# Heaters.net
KiCad netlist of a schematic drawn in Altium Designer
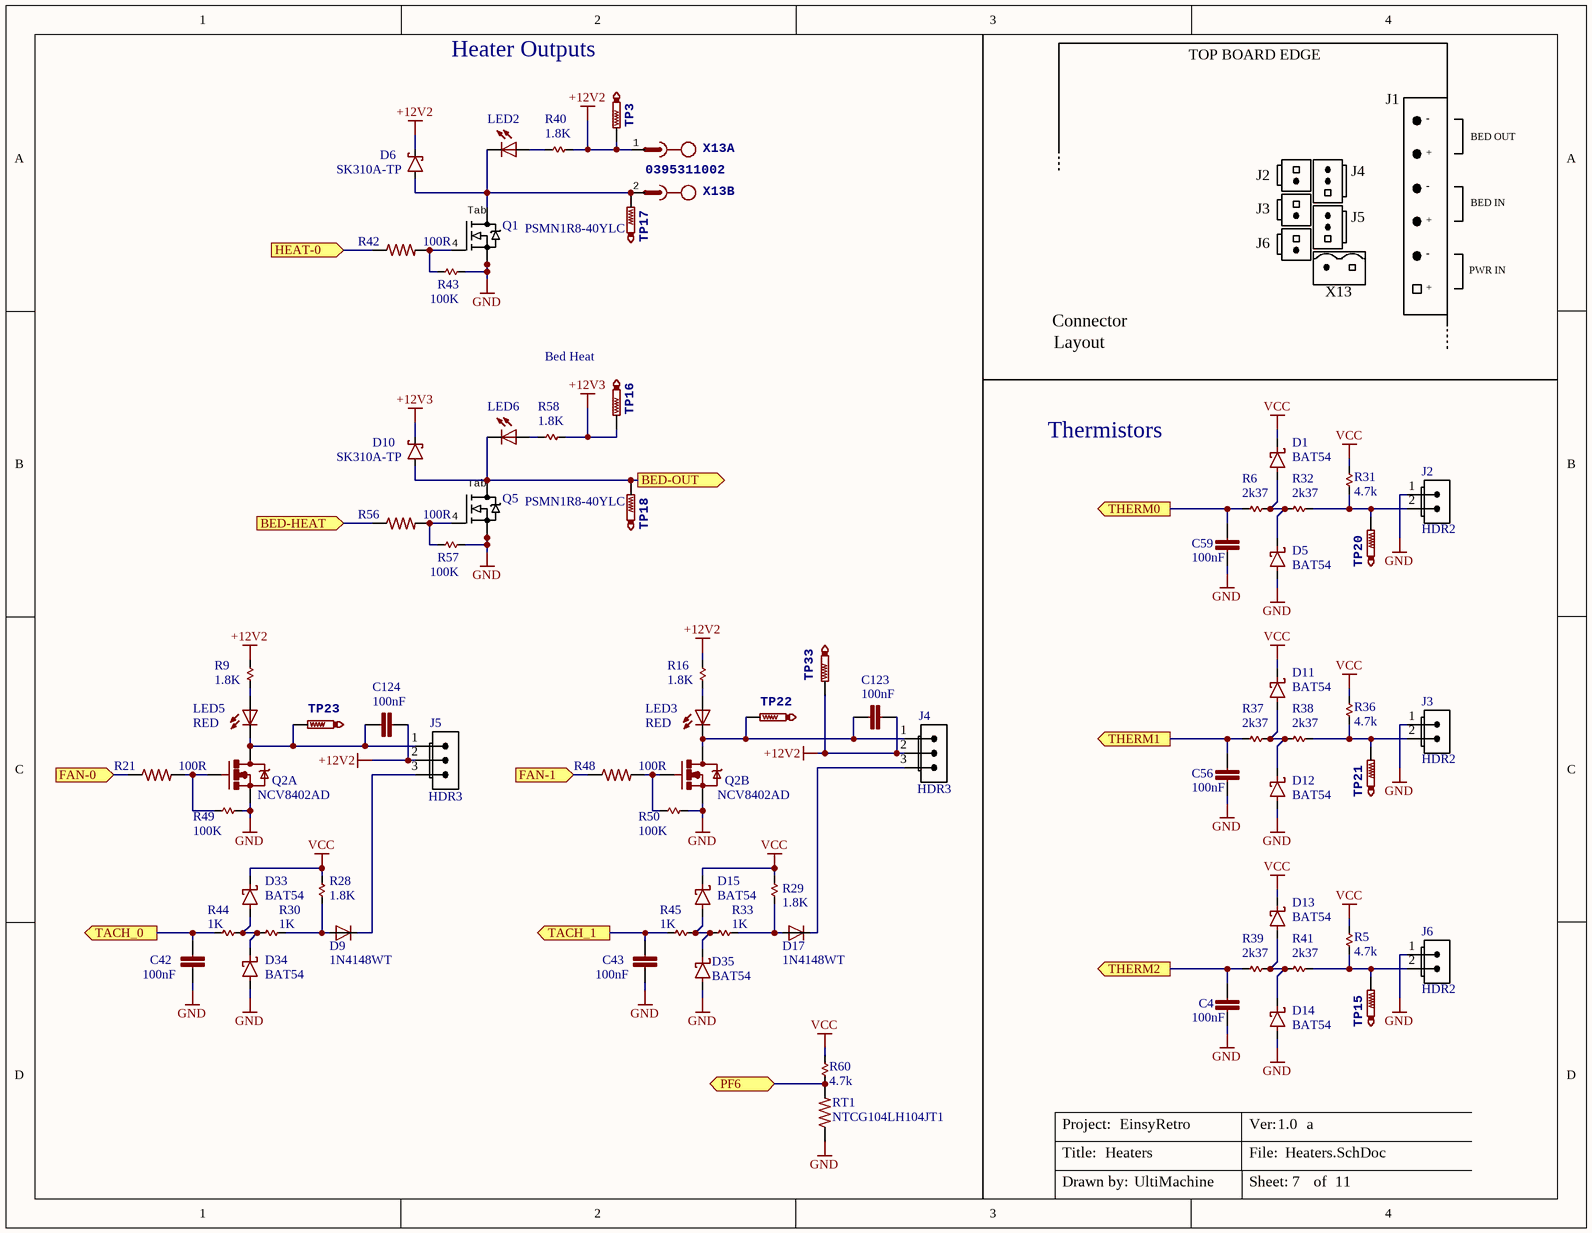
[diagram p0: Heaters.SchDoc]

(export (version "E")
  (design (tool "Eeschema 10.0.6"))
  (components
    (comp (ref "C4")
      (value "100nF")
      (footprint "C0402")
      (description "CAP CER 0402 100nF 16V 10% X7R")
      (fields (field (name "MANUFACTURER") "Murata") (field (name "TOLERANCE") "+/- 10%"))
      (libsource (lib "") (part "GRM155R71C104KA88D_1"))
    )
    (comp (ref "C42")
      (value "100nF")
      (footprint "C0402")
      (description "CAP CER 0402 100nF 16V 10% X7R")
      (fields (field (name "MANUFACTURER") "Murata") (field (name "TOLERANCE") "+/- 10%"))
      (libsource (lib "") (part "GRM155R71C104KA88D_1"))
    )
    (comp (ref "C43")
      (value "100nF")
      (footprint "C0402")
      (description "CAP CER 0402 100nF 16V 10% X7R")
      (fields (field (name "MANUFACTURER") "Murata") (field (name "TOLERANCE") "+/- 10%"))
      (libsource (lib "") (part "GRM155R71C104KA88D_1"))
    )
    (comp (ref "C56")
      (value "100nF")
      (footprint "C0402")
      (description "CAP CER 0402 100nF 16V 10% X7R")
      (fields (field (name "MANUFACTURER") "Murata") (field (name "TOLERANCE") "+/- 10%"))
      (libsource (lib "") (part "GRM155R71C104KA88D_1"))
    )
    (comp (ref "C59")
      (value "100nF")
      (footprint "C0402")
      (description "CAP CER 0402 100nF 16V 10% X7R")
      (fields (field (name "MANUFACTURER") "Murata") (field (name "TOLERANCE") "+/- 10%"))
      (libsource (lib "") (part "GRM155R71C104KA88D_1"))
    )
    (comp (ref "C123")
      (value "100nF")
      (footprint "C0402")
      (description "CAP CER 0402 100nF 16V 10% X7R")
      (fields (field (name "MANUFACTURER") "Murata") (field (name "TOLERANCE") "+/- 10%"))
      (libsource (lib "3Delight") (part "GRM155R71C104KA88D"))
    )
    (comp (ref "C124")
      (value "100nF")
      (footprint "C0402")
      (description "CAP CER 0402 100nF 16V 10% X7R")
      (fields (field (name "MANUFACTURER") "Murata") (field (name "TOLERANCE") "+/- 10%"))
      (libsource (lib "3Delight") (part "GRM155R71C104KA88D"))
    )
    (comp (ref "D1")
      (value "BAT54")
      (footprint "SOD523_IPC")
      (description "Diode Schottky 30V 100mA Surface Mount SOD-523")
      (fields (field (name "MANUFACTURER") "Diodes Incorporated") (field (name "TOLERANCE") "NA"))
      (libsource (lib "3Delight") (part "BAT54WT-7"))
    )
    (comp (ref "D5")
      (value "BAT54")
      (footprint "SOD523_IPC")
      (description "Diode Schottky 30V 100mA Surface Mount SOD-523")
      (fields (field (name "MANUFACTURER") "Diodes Incorporated") (field (name "TOLERANCE") "NA"))
      (libsource (lib "3Delight") (part "BAT54WT-7"))
    )
    (comp (ref "D6")
      (value "SK310A-TP")
      (footprint "SMA-SM")
      (description "DIODE Schottky 3A SMA")
      (fields (field (name "MANUFACTURER") "MCC") (field (name "PART") "Schottky Diode 100V 3A"))
      (libsource (lib "Diodes") (part "SK310A"))
    )
    (comp (ref "D9")
      (value "1N4148WT")
      (footprint "SOD523")
      (description "DIODE SOD523")
      (fields (field (name "MANUFACTURER") "Fairchild") (field (name "TOLERANCE") "NA"))
      (libsource (lib "3Delight") (part "1N4148WT"))
    )
    (comp (ref "D10")
      (value "SK310A-TP")
      (footprint "SMA-SM")
      (description "DIODE Schottky 3A SMA")
      (fields (field (name "MANUFACTURER") "MCC") (field (name "PART") "Schottky Diode 100V 3A"))
      (libsource (lib "Diodes") (part "SK310A"))
    )
    (comp (ref "D11")
      (value "BAT54")
      (footprint "SOD523_IPC")
      (description "Diode Schottky 30V 100mA Surface Mount SOD-523")
      (fields (field (name "MANUFACTURER") "Diodes Incorporated") (field (name "TOLERANCE") "NA"))
      (libsource (lib "3Delight") (part "BAT54WT-7"))
    )
    (comp (ref "D12")
      (value "BAT54")
      (footprint "SOD523_IPC")
      (description "Diode Schottky 30V 100mA Surface Mount SOD-523")
      (fields (field (name "MANUFACTURER") "Diodes Incorporated") (field (name "TOLERANCE") "NA"))
      (libsource (lib "3Delight") (part "BAT54WT-7"))
    )
    (comp (ref "D13")
      (value "BAT54")
      (footprint "SOD523_IPC")
      (description "Diode Schottky 30V 100mA Surface Mount SOD-523")
      (fields (field (name "MANUFACTURER") "Diodes Incorporated") (field (name "TOLERANCE") "NA"))
      (libsource (lib "3Delight") (part "BAT54WT-7"))
    )
    (comp (ref "D14")
      (value "BAT54")
      (footprint "SOD523_IPC")
      (description "Diode Schottky 30V 100mA Surface Mount SOD-523")
      (fields (field (name "MANUFACTURER") "Diodes Incorporated") (field (name "TOLERANCE") "NA"))
      (libsource (lib "3Delight") (part "BAT54WT-7"))
    )
    (comp (ref "D15")
      (value "BAT54")
      (footprint "SOD523_IPC")
      (description "Diode Schottky 30V 100mA Surface Mount SOD-523")
      (fields (field (name "MANUFACTURER") "Diodes Incorporated") (field (name "TOLERANCE") "NA"))
      (libsource (lib "3Delight") (part "BAT54WT-7"))
    )
    (comp (ref "D17")
      (value "1N4148WT")
      (footprint "SOD523")
      (description "DIODE SOD523")
      (fields (field (name "MANUFACTURER") "Fairchild") (field (name "TOLERANCE") "NA"))
      (libsource (lib "3Delight") (part "1N4148WT"))
    )
    (comp (ref "D33")
      (value "BAT54")
      (footprint "SOD523_IPC")
      (description "Diode Schottky 30V 100mA Surface Mount SOD-523")
      (fields (field (name "MANUFACTURER") "Diodes Incorporated") (field (name "TOLERANCE") "NA"))
      (libsource (lib "3Delight") (part "BAT54WT-7"))
    )
    (comp (ref "D34")
      (value "BAT54")
      (footprint "SOD523_IPC")
      (description "Diode Schottky 30V 100mA Surface Mount SOD-523")
      (fields (field (name "MANUFACTURER") "Diodes Incorporated") (field (name "TOLERANCE") "NA"))
      (libsource (lib "3Delight") (part "BAT54WT-7"))
    )
    (comp (ref "D35")
      (value "BAT54")
      (footprint "SOD523_IPC")
      (description "Diode Schottky 30V 100mA Surface Mount SOD-523")
      (fields (field (name "MANUFACTURER") "Diodes Incorporated") (field (name "TOLERANCE") "NA"))
      (libsource (lib "3Delight") (part "BAT54WT-7"))
    )
    (comp (ref "J2")
      (value "HDR2")
      (footprint "70543-02")
      (description "Connector 2pos")
      (fields (field (name "MANUFACTURER") "Molex") (field (name "PART") "10 Pin Conn"))
      (libsource (lib "Archim_0.4") (part "CONN 2PIN VERT 0.1{dblquote} SHRD LOCKING"))
    )
    (comp (ref "J3")
      (value "HDR2")
      (footprint "70543-02")
      (description "Connector 2pos")
      (fields (field (name "MANUFACTURER") "Molex") (field (name "PART") "10 Pin Conn"))
      (libsource (lib "Archim_0.4") (part "CONN 2PIN VERT 0.1{dblquote} SHRD LOCKING"))
    )
    (comp (ref "J4")
      (value "HDR3")
      (footprint "70543-03")
      (description "3 Positions Header, Shrouded Connector 0.100\" (2.54mm) Through Hole Gold")
      (fields (field (name "MANUFACTURER") "Molex") (field (name "PART") "3 Pin Conn VERT"))
      (libsource (lib "Archim_0.4") (part "CONN 3POS VERT 0.1{dblquote} SHRD LOCKING"))
    )
    (comp (ref "J5")
      (value "HDR3")
      (footprint "70543-03")
      (description "3 Positions Header, Shrouded Connector 0.100\" (2.54mm) Through Hole Gold")
      (fields (field (name "MANUFACTURER") "Molex") (field (name "PART") "3 Pin Conn VERT"))
      (libsource (lib "Archim_0.4") (part "CONN 3POS VERT 0.1{dblquote} SHRD LOCKING"))
    )
    (comp (ref "J6")
      (value "HDR2")
      (footprint "70543-02")
      (description "Connector 2pos")
      (fields (field (name "MANUFACTURER") "Molex") (field (name "PART") "10 Pin Conn"))
      (libsource (lib "Archim_0.4") (part "CONN 2PIN VERT 0.1{dblquote} SHRD LOCKING"))
    )
    (comp (ref "LED2")
      (value "RED")
      (footprint "LED2012120")
      (description "LED 0805 Red")
      (fields (field (name "MANUFACTURER") "Dialight") (field (name "TOLERANCE") "NA"))
      (libsource (lib "3Delight") (part "5988110107F"))
    )
    (comp (ref "LED3")
      (value "RED")
      (footprint "LED2012120")
      (description "LED 0805 Red")
      (fields
        (field (name "MANUFACTURER") "Dialight")
        (field (name "PART") "RED")
        (field (name "TOLERANCE") "NA")
      )
      (libsource (lib "3Delight") (part "5988110107F"))
    )
    (comp (ref "LED5")
      (value "RED")
      (footprint "LED2012120")
      (description "LED 0805 Red")
      (fields
        (field (name "MANUFACTURER") "Dialight")
        (field (name "PART") "RED")
        (field (name "TOLERANCE") "NA")
      )
      (libsource (lib "3Delight") (part "5988110107F"))
    )
    (comp (ref "LED6")
      (value "RED")
      (footprint "LED2012120")
      (description "LED 0805 Red")
      (fields (field (name "MANUFACTURER") "Dialight") (field (name "TOLERANCE") "NA"))
      (libsource (lib "3Delight") (part "5988110107F"))
    )
    (comp (ref "Q1")
      (value "PSMN1R8-40YLC")
      (footprint "SOT669")
      (description "MOSFET N-CH 40V 100A LFPAK")
      (fields (field (name "MANUFACTURER") "Nexperia") (field (name "TOLERANCE") "-NA-"))
      (libsource (lib "Transistors") (part "PSMN1R8-40YLC"))
    )
    (comp (ref "Q2")
      (value "NCV8402AD")
      (footprint "NCV8402AD-SOIC8")
      (description "IC DVR LOW SIDE 8-SOIC")
      (fields (field (name "MANUFACTURER") "On Semi") (field (name "PART") "NCV8402"))
      (libsource (lib "3Delight") (part "NCV8402AD"))
    )
    (comp (ref "Q5")
      (value "PSMN1R8-40YLC")
      (footprint "SOT669")
      (description "MOSFET N-CH 40V 100A LFPAK")
      (fields (field (name "MANUFACTURER") "Nexperia") (field (name "TOLERANCE") "-NA-"))
      (libsource (lib "Transistors") (part "PSMN1R8-40YLC"))
    )
    (comp (ref "R5")
      (value "4.7k")
      (footprint "R0402")
      (description "RES SMD 4.7K OHM 1% 1/16W 0402")
      (fields (field (name "MANUFACTURER") "Yageo") (field (name "TOLERANCE") "+/- 1%"))
      (libsource (lib "3Delight") (part "RC0402FR-074K7L"))
    )
    (comp (ref "R6")
      (value "2k37")
      (footprint "R0402")
      (description "RES SMD 2.37K OHM 1% 1/16W 0402")
      (fields (field (name "MANUFACTURER") "Yageo") (field (name "PART") "2.37k"))
      (libsource (lib "3Delight") (part "RC0402FR-072K37L"))
    )
    (comp (ref "R9")
      (value "1.8K")
      (footprint "R0402")
      (description "RES SMD 1.8K OHM 1% 1/16W 0402")
      (fields (field (name "MANUFACTURER") "Yageo") (field (name "PART") "1.8k"))
      (libsource (lib "3Delight") (part "RC0402FR-071K8L"))
    )
    (comp (ref "R16")
      (value "1.8K")
      (footprint "R0402")
      (description "RES SMD 1.8K OHM 1% 1/16W 0402")
      (fields (field (name "MANUFACTURER") "Yageo") (field (name "PART") "1.8k"))
      (libsource (lib "3Delight") (part "RC0402FR-071K8L"))
    )
    (comp (ref "R21")
      (value "100R")
      (footprint "R0402")
      (description "RES SMD 100 OHM 1% 1/16W 0402")
      (fields (field (name "MANUFACTURER") "Yageo") (field (name "PART") "100R 1% 0402"))
      (libsource (lib "Archim") (part "RES 100R 0402 1%"))
    )
    (comp (ref "R28")
      (value "1.8K")
      (footprint "R0402")
      (description "RES SMD 1.8K OHM 1% 1/16W 0402")
      (fields (field (name "MANUFACTURER") "Yageo") (field (name "PART") "1.8k"))
      (libsource (lib "3Delight") (part "RC0402FR-071K8L"))
    )
    (comp (ref "R29")
      (value "1.8K")
      (footprint "R0402")
      (description "RES SMD 1.8K OHM 1% 1/16W 0402")
      (fields (field (name "MANUFACTURER") "Yageo") (field (name "PART") "1.8k"))
      (libsource (lib "3Delight") (part "RC0402FR-071K8L"))
    )
    (comp (ref "R30")
      (value "1K")
      (footprint "R0402")
      (description "RES SMD 1K OHM 1% 1/16W 0402")
      (fields (field (name "MANUFACTURER") "Yageo") (field (name "PART") "1k"))
      (libsource (lib "3Delight") (part "RC0402FR-071KL"))
    )
    (comp (ref "R31")
      (value "4.7k")
      (footprint "R0402")
      (description "RES SMD 4.7K OHM 1% 1/16W 0402")
      (fields (field (name "MANUFACTURER") "Yageo") (field (name "TOLERANCE") "+/- 1%"))
      (libsource (lib "3Delight") (part "RC0402FR-074K7L"))
    )
    (comp (ref "R32")
      (value "2k37")
      (footprint "R0402")
      (description "RES SMD 2.37K OHM 1% 1/16W 0402")
      (fields (field (name "MANUFACTURER") "Yageo") (field (name "PART") "2.37k"))
      (libsource (lib "3Delight") (part "RC0402FR-072K37L"))
    )
    (comp (ref "R33")
      (value "1K")
      (footprint "R0402")
      (description "RES SMD 1K OHM 1% 1/16W 0402")
      (fields (field (name "MANUFACTURER") "Yageo") (field (name "PART") "1k"))
      (libsource (lib "3Delight") (part "RC0402FR-071KL"))
    )
    (comp (ref "R36")
      (value "4.7k")
      (footprint "R0402")
      (description "RES SMD 4.7K OHM 1% 1/16W 0402")
      (fields (field (name "MANUFACTURER") "Yageo") (field (name "TOLERANCE") "+/- 1%"))
      (libsource (lib "3Delight") (part "RC0402FR-074K7L"))
    )
    (comp (ref "R37")
      (value "2k37")
      (footprint "R0402")
      (description "RES SMD 2.37K OHM 1% 1/16W 0402")
      (fields (field (name "MANUFACTURER") "Yageo") (field (name "PART") "2.37k"))
      (libsource (lib "3Delight") (part "RC0402FR-072K37L"))
    )
    (comp (ref "R38")
      (value "2k37")
      (footprint "R0402")
      (description "RES SMD 2.37K OHM 1% 1/16W 0402")
      (fields (field (name "MANUFACTURER") "Yageo") (field (name "PART") "2.37k"))
      (libsource (lib "3Delight") (part "RC0402FR-072K37L"))
    )
    (comp (ref "R39")
      (value "2k37")
      (footprint "R0402")
      (description "RES SMD 2.37K OHM 1% 1/16W 0402")
      (fields (field (name "MANUFACTURER") "Yageo") (field (name "PART") "2.37k"))
      (libsource (lib "3Delight") (part "RC0402FR-072K37L"))
    )
    (comp (ref "R40")
      (value "1.8K")
      (footprint "R0402")
      (description "RES SMD 1.8K OHM 1% 1/16W 0402")
      (fields (field (name "MANUFACTURER") "Yageo") (field (name "PART") "1.8k"))
      (libsource (lib "3Delight") (part "RC0402FR-071K8L"))
    )
    (comp (ref "R41")
      (value "2k37")
      (footprint "R0402")
      (description "RES SMD 2.37K OHM 1% 1/16W 0402")
      (fields (field (name "MANUFACTURER") "Yageo") (field (name "PART") "2.37k"))
      (libsource (lib "3Delight") (part "RC0402FR-072K37L"))
    )
    (comp (ref "R42")
      (value "100R")
      (footprint "R0402")
      (description "RES SMD 100 OHM 1% 1/16W 0402")
      (fields (field (name "MANUFACTURER") "Yageo") (field (name "PART") "100R 1% 0402"))
      (libsource (lib "Archim") (part "RES 100R 0402 1%"))
    )
    (comp (ref "R43")
      (value "100K")
      (footprint "R0402")
      (description "RES 100K OHM 1% 1/16W 0402")
      (fields (field (name "MANUFACTURER") "Yageo") (field (name "TOLERANCE") "+/- 1%"))
      (libsource (lib "3Delight") (part "RC0402FR-07100KL"))
    )
    (comp (ref "R44")
      (value "1K")
      (footprint "R0402")
      (description "RES SMD 1K OHM 1% 1/16W 0402")
      (fields (field (name "MANUFACTURER") "Yageo") (field (name "PART") "1k"))
      (libsource (lib "3Delight") (part "RC0402FR-071KL"))
    )
    (comp (ref "R45")
      (value "1K")
      (footprint "R0402")
      (description "RES SMD 1K OHM 1% 1/16W 0402")
      (fields (field (name "MANUFACTURER") "Yageo") (field (name "PART") "1k"))
      (libsource (lib "3Delight") (part "RC0402FR-071KL"))
    )
    (comp (ref "R48")
      (value "100R")
      (footprint "R0402")
      (description "RES SMD 100 OHM 1% 1/16W 0402")
      (fields (field (name "MANUFACTURER") "Yageo") (field (name "PART") "100R 1% 0402"))
      (libsource (lib "Archim") (part "RES 100R 0402 1%"))
    )
    (comp (ref "R49")
      (value "100K")
      (footprint "R0402")
      (description "RES 100K OHM 1% 1/16W 0402")
      (fields (field (name "MANUFACTURER") "Yageo") (field (name "TOLERANCE") "+/- 1%"))
      (libsource (lib "3Delight") (part "RC0402FR-07100KL"))
    )
    (comp (ref "R50")
      (value "100K")
      (footprint "R0402")
      (description "RES 100K OHM 1% 1/16W 0402")
      (fields (field (name "MANUFACTURER") "Yageo") (field (name "TOLERANCE") "+/- 1%"))
      (libsource (lib "3Delight") (part "RC0402FR-07100KL"))
    )
    (comp (ref "R56")
      (value "100R")
      (footprint "R0402")
      (description "RES SMD 100 OHM 1% 1/16W 0402")
      (fields (field (name "MANUFACTURER") "Yageo") (field (name "PART") "100R 1% 0402"))
      (libsource (lib "Archim") (part "RES 100R 0402 1%"))
    )
    (comp (ref "R57")
      (value "100K")
      (footprint "R0402")
      (description "RES 100K OHM 1% 1/16W 0402")
      (fields (field (name "MANUFACTURER") "Yageo") (field (name "TOLERANCE") "+/- 1%"))
      (libsource (lib "3Delight") (part "RC0402FR-07100KL"))
    )
    (comp (ref "R58")
      (value "1.8K")
      (footprint "R0402")
      (description "RES SMD 1.8K OHM 1% 1/16W 0402")
      (fields (field (name "MANUFACTURER") "Yageo") (field (name "PART") "1.8k"))
      (libsource (lib "3Delight") (part "RC0402FR-071K8L"))
    )
    (comp (ref "R60")
      (value "4.7k")
      (footprint "R0402")
      (description "RES SMD 4.7K OHM 1% 1/16W 0402")
      (fields (field (name "MANUFACTURER") "Yageo") (field (name "TOLERANCE") "+/- 1%"))
      (libsource (lib "3Delight") (part "RC0402FR-074K7L"))
    )
    (comp (ref "RT1")
      (value "NTCG104LH104JT1")
      (footprint "R0402")
      (description "Resistor")
      (fields (field (name "PUBLISHER") "UltiMachine"))
      (libsource (lib "3Delight") (part "R0402TBD"))
    )
    (comp (ref "TP3")
      (value "TestPoint")
      (footprint "TP1-27")
      (description "Test Point")
      (libsource (lib "") (part "TestPoint_1"))
    )
    (comp (ref "TP15")
      (value "TestPoint")
      (footprint "TP1-27")
      (description "Test Point")
      (libsource (lib "") (part "TestPoint_2"))
    )
    (comp (ref "TP16")
      (value "TestPoint")
      (footprint "TP1-27")
      (description "Test Point")
      (libsource (lib "") (part "TestPoint_1"))
    )
    (comp (ref "TP17")
      (value "TestPoint")
      (footprint "TP1-27")
      (description "Test Point")
      (libsource (lib "") (part "TestPoint_2"))
    )
    (comp (ref "TP18")
      (value "TestPoint")
      (footprint "TP1-27")
      (description "Test Point")
      (libsource (lib "") (part "TestPoint_2"))
    )
    (comp (ref "TP20")
      (value "TestPoint")
      (footprint "TP1-27")
      (description "Test Point")
      (libsource (lib "") (part "TestPoint_2"))
    )
    (comp (ref "TP21")
      (value "TestPoint")
      (footprint "TP1-27")
      (description "Test Point")
      (libsource (lib "") (part "TestPoint_2"))
    )
    (comp (ref "TP22")
      (value "TestPoint")
      (footprint "TP1-27")
      (description "Test Point")
      (libsource (lib "3Delight") (part "TestPoint"))
    )
    (comp (ref "TP23")
      (value "TestPoint")
      (footprint "TP1-27")
      (description "Test Point")
      (libsource (lib "3Delight") (part "TestPoint"))
    )
    (comp (ref "TP33")
      (value "TestPoint")
      (footprint "TP1-27")
      (description "Test Point")
      (libsource (lib "") (part "TestPoint_1"))
    )
    (comp (ref "X13")
      (value "0395311002")
      (footprint "MSTBV2")
      (description "Conn - 5.08mm Pitch Fixed")
      (fields (field (name "MANUFACTURER") "Molex") (field (name "PART") "2POS"))
      (libsource (lib "") (part "0395311002_1"))
    )
  )
  (nets
    (net (code "1") (name "+12V2") (class "Default")
      (node (ref "C123") (pin "2") (pinfunction "2_2") (pintype "passive"))
      (node (ref "C124") (pin "2") (pinfunction "2_2") (pintype "passive"))
      (node (ref "D6") (pin "K") (pinfunction "K_K") (pintype "passive"))
      (node (ref "J4") (pin "2") (pinfunction "S_2") (pintype "passive"))
      (node (ref "J5") (pin "2") (pinfunction "S_2") (pintype "passive"))
      (node (ref "R16") (pin "1") (pinfunction "1_1") (pintype "passive"))
      (node (ref "R40") (pin "1") (pinfunction "1_1") (pintype "passive"))
      (node (ref "R9") (pin "1") (pinfunction "1_1") (pintype "passive"))
      (node (ref "TP3") (pin "TP") (pinfunction "TP_TP") (pintype "passive"))
      (node (ref "TP33") (pin "TP") (pinfunction "TP_TP") (pintype "passive"))
      (node (ref "X13") (pin "1") (pinfunction "1_1") (pintype "passive"))
    )
    (net (code "2") (name "+12V3") (class "Default")
      (node (ref "D10") (pin "K") (pinfunction "K_K") (pintype "passive"))
      (node (ref "R58") (pin "1") (pinfunction "1_1") (pintype "passive"))
      (node (ref "TP16") (pin "TP") (pinfunction "TP_TP") (pintype "passive"))
    )
    (net (code "3") (name "/BED-HEAT") (class "Default")
      (node (ref "R56") (pin "1") (pinfunction "1_1") (pintype "passive"))
    )
    (net (code "4") (name "/BED-OUT") (class "Default")
      (node (ref "D10") (pin "A") (pinfunction "A_A") (pintype "passive"))
      (node (ref "LED6") (pin "C") (pinfunction "C_C") (pintype "passive"))
      (node (ref "Q5") (pin "MB") (pinfunction "D_MB") (pintype "passive"))
      (node (ref "TP18") (pin "TP") (pinfunction "TP_TP") (pintype "passive"))
    )
    (net (code "5") (name "/FAN-0") (class "Default")
      (node (ref "R21") (pin "1") (pinfunction "1_1") (pintype "passive"))
    )
    (net (code "6") (name "/FAN-1") (class "Default")
      (node (ref "R48") (pin "1") (pinfunction "1_1") (pintype "passive"))
    )
    (net (code "7") (name "/HEAT-0") (class "Default")
      (node (ref "R42") (pin "1") (pinfunction "1_1") (pintype "passive"))
    )
    (net (code "8") (name "/PF6") (class "Default")
      (node (ref "R60") (pin "1") (pinfunction "1_1") (pintype "passive"))
      (node (ref "RT1") (pin "2") (pinfunction "2_2") (pintype "passive"))
    )
    (net (code "9") (name "/TACH_0") (class "Default")
      (node (ref "C42") (pin "1") (pinfunction "1_1") (pintype "passive"))
      (node (ref "R44") (pin "1") (pinfunction "1_1") (pintype "passive"))
    )
    (net (code "10") (name "/TACH_1") (class "Default")
      (node (ref "C43") (pin "1") (pinfunction "1_1") (pintype "passive"))
      (node (ref "R45") (pin "1") (pinfunction "1_1") (pintype "passive"))
    )
    (net (code "11") (name "/THERM0") (class "Default")
      (node (ref "C59") (pin "1") (pinfunction "1_1") (pintype "passive"))
      (node (ref "R6") (pin "2") (pinfunction "2_2") (pintype "passive"))
    )
    (net (code "12") (name "/THERM1") (class "Default")
      (node (ref "C56") (pin "1") (pinfunction "1_1") (pintype "passive"))
      (node (ref "R37") (pin "2") (pinfunction "2_2") (pintype "passive"))
    )
    (net (code "13") (name "/THERM2") (class "Default")
      (node (ref "C4") (pin "1") (pinfunction "1_1") (pintype "passive"))
      (node (ref "R39") (pin "2") (pinfunction "2_2") (pintype "passive"))
    )
    (net (code "14") (name "GND") (class "Default")
      (node (ref "C4") (pin "2") (pinfunction "2_2") (pintype "passive"))
      (node (ref "C42") (pin "2") (pinfunction "2_2") (pintype "passive"))
      (node (ref "C43") (pin "2") (pinfunction "2_2") (pintype "passive"))
      (node (ref "C56") (pin "2") (pinfunction "2_2") (pintype "passive"))
      (node (ref "C59") (pin "2") (pinfunction "2_2") (pintype "passive"))
      (node (ref "D12") (pin "A") (pinfunction "A_A") (pintype "passive"))
      (node (ref "D14") (pin "A") (pinfunction "A_A") (pintype "passive"))
      (node (ref "D34") (pin "A") (pinfunction "A_A") (pintype "passive"))
      (node (ref "D35") (pin "A") (pinfunction "A_A") (pintype "passive"))
      (node (ref "D5") (pin "A") (pinfunction "A_A") (pintype "passive"))
      (node (ref "J2") (pin "1") (pinfunction "S_1") (pintype "passive"))
      (node (ref "J3") (pin "1") (pinfunction "S_1") (pintype "passive"))
      (node (ref "J6") (pin "1") (pinfunction "S_1") (pintype "passive"))
      (node (ref "Q1") (pin "1") (pinfunction "S_1") (pintype "passive"))
      (node (ref "Q1") (pin "2") (pinfunction "S_2") (pintype "passive"))
      (node (ref "Q1") (pin "3") (pinfunction "S_3") (pintype "passive"))
      (node (ref "Q2") (pin "1") (pinfunction "S_1") (pintype "passive"))
      (node (ref "Q2") (pin "3") (pinfunction "S_3") (pintype "passive"))
      (node (ref "Q5") (pin "1") (pinfunction "S_1") (pintype "passive"))
      (node (ref "Q5") (pin "2") (pinfunction "S_2") (pintype "passive"))
      (node (ref "Q5") (pin "3") (pinfunction "S_3") (pintype "passive"))
      (node (ref "R43") (pin "1") (pinfunction "1_1") (pintype "passive"))
      (node (ref "R49") (pin "2") (pinfunction "2_2") (pintype "passive"))
      (node (ref "R50") (pin "2") (pinfunction "2_2") (pintype "passive"))
      (node (ref "R57") (pin "1") (pinfunction "1_1") (pintype "passive"))
      (node (ref "RT1") (pin "1") (pinfunction "1_1") (pintype "passive"))
    )
    (net (code "15") (name "Net-(D1-PadA)") (class "Default")
      (node (ref "D1") (pin "A") (pinfunction "A_A") (pintype "passive"))
      (node (ref "D5") (pin "K") (pinfunction "K_K") (pintype "passive"))
      (node (ref "R32") (pin "2") (pinfunction "2_2") (pintype "passive"))
      (node (ref "R6") (pin "1") (pinfunction "1_1") (pintype "passive"))
    )
    (net (code "16") (name "Net-(D9-PadA)") (class "Default")
      (node (ref "D9") (pin "A") (pinfunction "A_A") (pintype "passive"))
      (node (ref "R28") (pin "1") (pinfunction "1_1") (pintype "passive"))
      (node (ref "R30") (pin "2") (pinfunction "2_2") (pintype "passive"))
    )
    (net (code "17") (name "Net-(D9-PadC)") (class "Default")
      (node (ref "D9") (pin "C") (pinfunction "C_C") (pintype "passive"))
      (node (ref "J5") (pin "3") (pinfunction "S_3") (pintype "passive"))
    )
    (net (code "18") (name "Net-(D11-PadA)") (class "Default")
      (node (ref "D11") (pin "A") (pinfunction "A_A") (pintype "passive"))
      (node (ref "D12") (pin "K") (pinfunction "K_K") (pintype "passive"))
      (node (ref "R37") (pin "1") (pinfunction "1_1") (pintype "passive"))
      (node (ref "R38") (pin "2") (pinfunction "2_2") (pintype "passive"))
    )
    (net (code "19") (name "Net-(D13-PadA)") (class "Default")
      (node (ref "D13") (pin "A") (pinfunction "A_A") (pintype "passive"))
      (node (ref "D14") (pin "K") (pinfunction "K_K") (pintype "passive"))
      (node (ref "R39") (pin "1") (pinfunction "1_1") (pintype "passive"))
      (node (ref "R41") (pin "2") (pinfunction "2_2") (pintype "passive"))
    )
    (net (code "20") (name "Net-(D15-PadA)") (class "Default")
      (node (ref "D15") (pin "A") (pinfunction "A_A") (pintype "passive"))
      (node (ref "D35") (pin "K") (pinfunction "K_K") (pintype "passive"))
      (node (ref "R33") (pin "1") (pinfunction "1_1") (pintype "passive"))
      (node (ref "R45") (pin "2") (pinfunction "2_2") (pintype "passive"))
    )
    (net (code "21") (name "Net-(D17-PadA)") (class "Default")
      (node (ref "D17") (pin "A") (pinfunction "A_A") (pintype "passive"))
      (node (ref "R29") (pin "1") (pinfunction "1_1") (pintype "passive"))
      (node (ref "R33") (pin "2") (pinfunction "2_2") (pintype "passive"))
    )
    (net (code "22") (name "Net-(D17-PadC)") (class "Default")
      (node (ref "D17") (pin "C") (pinfunction "C_C") (pintype "passive"))
      (node (ref "J4") (pin "3") (pinfunction "S_3") (pintype "passive"))
    )
    (net (code "23") (name "Net-(D33-PadA)") (class "Default")
      (node (ref "D33") (pin "A") (pinfunction "A_A") (pintype "passive"))
      (node (ref "D34") (pin "K") (pinfunction "K_K") (pintype "passive"))
      (node (ref "R30") (pin "1") (pinfunction "1_1") (pintype "passive"))
      (node (ref "R44") (pin "2") (pinfunction "2_2") (pintype "passive"))
    )
    (net (code "24") (name "Net-(J2-S-Pad2)") (class "Default")
      (node (ref "J2") (pin "2") (pinfunction "S_2") (pintype "passive"))
      (node (ref "R31") (pin "1") (pinfunction "1_1") (pintype "passive"))
      (node (ref "R32") (pin "1") (pinfunction "1_1") (pintype "passive"))
      (node (ref "TP20") (pin "TP") (pinfunction "TP_TP") (pintype "passive"))
    )
    (net (code "25") (name "Net-(J3-S-Pad2)") (class "Default")
      (node (ref "J3") (pin "2") (pinfunction "S_2") (pintype "passive"))
      (node (ref "R36") (pin "1") (pinfunction "1_1") (pintype "passive"))
      (node (ref "R38") (pin "1") (pinfunction "1_1") (pintype "passive"))
      (node (ref "TP21") (pin "TP") (pinfunction "TP_TP") (pintype "passive"))
    )
    (net (code "26") (name "Net-(J6-S-Pad2)") (class "Default")
      (node (ref "J6") (pin "2") (pinfunction "S_2") (pintype "passive"))
      (node (ref "R41") (pin "1") (pinfunction "1_1") (pintype "passive"))
      (node (ref "R5") (pin "1") (pinfunction "1_1") (pintype "passive"))
      (node (ref "TP15") (pin "TP") (pinfunction "TP_TP") (pintype "passive"))
    )
    (net (code "27") (name "Net-(LED2-PadA)") (class "Default")
      (node (ref "LED2") (pin "A") (pinfunction "A_A") (pintype "passive"))
      (node (ref "R40") (pin "2") (pinfunction "2_2") (pintype "passive"))
    )
    (net (code "28") (name "Net-(LED3-PadA)") (class "Default")
      (node (ref "LED3") (pin "A") (pinfunction "A_A") (pintype "passive"))
      (node (ref "R16") (pin "2") (pinfunction "2_2") (pintype "passive"))
    )
    (net (code "29") (name "Net-(LED5-PadA)") (class "Default")
      (node (ref "LED5") (pin "A") (pinfunction "A_A") (pintype "passive"))
      (node (ref "R9") (pin "2") (pinfunction "2_2") (pintype "passive"))
    )
    (net (code "30") (name "Net-(LED6-PadA)") (class "Default")
      (node (ref "LED6") (pin "A") (pinfunction "A_A") (pintype "passive"))
      (node (ref "R58") (pin "2") (pinfunction "2_2") (pintype "passive"))
    )
    (net (code "31") (name "Net-(Q1-D)") (class "Default")
      (node (ref "D6") (pin "A") (pinfunction "A_A") (pintype "passive"))
      (node (ref "LED2") (pin "C") (pinfunction "C_C") (pintype "passive"))
      (node (ref "Q1") (pin "MB") (pinfunction "D_MB") (pintype "passive"))
      (node (ref "TP17") (pin "TP") (pinfunction "TP_TP") (pintype "passive"))
      (node (ref "X13") (pin "2") (pinfunction "1_2") (pintype "passive"))
    )
    (net (code "32") (name "Net-(Q1-G)") (class "Default")
      (node (ref "Q1") (pin "4") (pinfunction "G_4") (pintype "passive"))
      (node (ref "R42") (pin "2") (pinfunction "2_2") (pintype "passive"))
      (node (ref "R43") (pin "2") (pinfunction "2_2") (pintype "passive"))
    )
    (net (code "33") (name "Net-(Q2A-D)") (class "Default")
      (node (ref "C124") (pin "1") (pinfunction "1_1") (pintype "passive"))
      (node (ref "J5") (pin "1") (pinfunction "S_1") (pintype "passive"))
      (node (ref "LED5") (pin "C") (pinfunction "C_C") (pintype "passive"))
      (node (ref "Q2") (pin "7") (pinfunction "D_7") (pintype "passive"))
      (node (ref "TP23") (pin "TP") (pinfunction "TP_TP") (pintype "passive"))
    )
    (net (code "34") (name "Net-(Q2A-G)") (class "Default")
      (node (ref "Q2") (pin "2") (pinfunction "G_2") (pintype "passive"))
      (node (ref "R21") (pin "2") (pinfunction "2_2") (pintype "passive"))
      (node (ref "R49") (pin "1") (pinfunction "1_1") (pintype "passive"))
    )
    (net (code "35") (name "Net-(Q2B-D)") (class "Default")
      (node (ref "C123") (pin "1") (pinfunction "1_1") (pintype "passive"))
      (node (ref "J4") (pin "1") (pinfunction "S_1") (pintype "passive"))
      (node (ref "LED3") (pin "C") (pinfunction "C_C") (pintype "passive"))
      (node (ref "Q2") (pin "5") (pinfunction "D_5") (pintype "passive"))
      (node (ref "TP22") (pin "TP") (pinfunction "TP_TP") (pintype "passive"))
    )
    (net (code "36") (name "Net-(Q2B-G)") (class "Default")
      (node (ref "Q2") (pin "4") (pinfunction "G_4") (pintype "passive"))
      (node (ref "R48") (pin "2") (pinfunction "2_2") (pintype "passive"))
      (node (ref "R50") (pin "1") (pinfunction "1_1") (pintype "passive"))
    )
    (net (code "37") (name "Net-(Q5-G)") (class "Default")
      (node (ref "Q5") (pin "4") (pinfunction "G_4") (pintype "passive"))
      (node (ref "R56") (pin "2") (pinfunction "2_2") (pintype "passive"))
      (node (ref "R57") (pin "2") (pinfunction "2_2") (pintype "passive"))
    )
    (net (code "38") (name "VCC") (class "Default")
      (node (ref "D1") (pin "K") (pinfunction "K_K") (pintype "passive"))
      (node (ref "D11") (pin "K") (pinfunction "K_K") (pintype "passive"))
      (node (ref "D13") (pin "K") (pinfunction "K_K") (pintype "passive"))
      (node (ref "D15") (pin "K") (pinfunction "K_K") (pintype "passive"))
      (node (ref "D33") (pin "K") (pinfunction "K_K") (pintype "passive"))
      (node (ref "R28") (pin "2") (pinfunction "2_2") (pintype "passive"))
      (node (ref "R29") (pin "2") (pinfunction "2_2") (pintype "passive"))
      (node (ref "R31") (pin "2") (pinfunction "2_2") (pintype "passive"))
      (node (ref "R36") (pin "2") (pinfunction "2_2") (pintype "passive"))
      (node (ref "R5") (pin "2") (pinfunction "2_2") (pintype "passive"))
      (node (ref "R60") (pin "2") (pinfunction "2_2") (pintype "passive"))
    )
  )
)
